# wifi-gps.net
KiCad netlist of a schematic drawn in Altium Designer
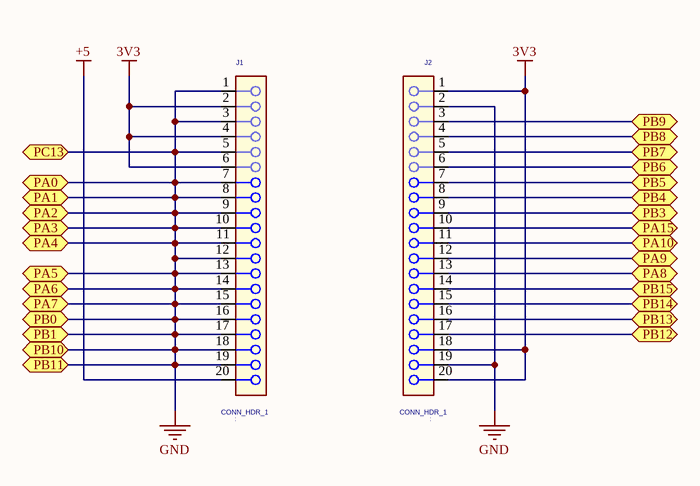
[diagram p0: wifi-gps.SchDoc]

(export (version "E")
  (design (tool "Eeschema 10.0.6"))
  (components
    (comp (ref "J1")
      (value "CONN_HDR_1")
      (footprint "SIP20-2P54-F")
      (description "CON 1X6 SKT TH 100MIL SP 344H AU 118L")
      (fields (field (name "SOURCE") "野火_STM32F103C8T6核心板_V1.0_原理图封装库_AD格式.SCHLIB"))
      (libsource (lib "yuanyu") (part "CONN_HDR_1"))
    )
    (comp (ref "J2")
      (value "CONN_HDR_1")
      (footprint "SIP20-2P54-F")
      (description "CON 1X6 SKT TH 100MIL SP 344H AU 118L")
      (fields (field (name "SOURCE") "野火_STM32F103C8T6核心板_V1.0_原理图封装库_AD格式.SCHLIB"))
      (libsource (lib "yuanyu") (part "CONN_HDR_1"))
    )
  )
  (nets
    (net (code "1") (name "+5") (class "Default")
      (node (ref "J1") (pin "20") (pinfunction "20_20") (pintype "passive"))
    )
    (net (code "2") (name "/PA8") (class "Default")
      (node (ref "J2") (pin "13") (pinfunction "13_13") (pintype "passive"))
    )
    (net (code "3") (name "/PA9") (class "Default")
      (node (ref "J2") (pin "12") (pinfunction "12_12") (pintype "passive"))
    )
    (net (code "4") (name "/PA10") (class "Default")
      (node (ref "J2") (pin "11") (pinfunction "11_11") (pintype "passive"))
    )
    (net (code "5") (name "/PA15") (class "Default")
      (node (ref "J2") (pin "10") (pinfunction "10_10") (pintype "passive"))
    )
    (net (code "6") (name "/PB3") (class "Default")
      (node (ref "J2") (pin "9") (pinfunction "9_9") (pintype "passive"))
    )
    (net (code "7") (name "/PB4") (class "Default")
      (node (ref "J2") (pin "8") (pinfunction "8_8") (pintype "passive"))
    )
    (net (code "8") (name "/PB5") (class "Default")
      (node (ref "J2") (pin "7") (pinfunction "7_7") (pintype "passive"))
    )
    (net (code "9") (name "/PB6") (class "Default")
      (node (ref "J2") (pin "6") (pinfunction "6_6") (pintype "passive"))
    )
    (net (code "10") (name "/PB7") (class "Default")
      (node (ref "J2") (pin "5") (pinfunction "5_5") (pintype "passive"))
    )
    (net (code "11") (name "/PB8") (class "Default")
      (node (ref "J2") (pin "4") (pinfunction "4_4") (pintype "passive"))
    )
    (net (code "12") (name "/PB9") (class "Default")
      (node (ref "J2") (pin "3") (pinfunction "3_3") (pintype "passive"))
    )
    (net (code "13") (name "/PB12") (class "Default")
      (node (ref "J2") (pin "17") (pinfunction "17_17") (pintype "passive"))
    )
    (net (code "14") (name "/PB13") (class "Default")
      (node (ref "J2") (pin "16") (pinfunction "16_16") (pintype "passive"))
    )
    (net (code "15") (name "/PB14") (class "Default")
      (node (ref "J2") (pin "15") (pinfunction "15_15") (pintype "passive"))
    )
    (net (code "16") (name "/PB15") (class "Default")
      (node (ref "J2") (pin "14") (pinfunction "14_14") (pintype "passive"))
    )
    (net (code "17") (name "3V3") (class "Default")
      (node (ref "J1") (pin "2") (pinfunction "2_2") (pintype "passive"))
      (node (ref "J1") (pin "4") (pinfunction "4_4") (pintype "passive"))
      (node (ref "J1") (pin "6") (pinfunction "6_6") (pintype "passive"))
      (node (ref "J2") (pin "1") (pinfunction "1_1") (pintype "passive"))
      (node (ref "J2") (pin "18") (pinfunction "18_18") (pintype "passive"))
      (node (ref "J2") (pin "20") (pinfunction "20_20") (pintype "passive"))
    )
    (net (code "18") (name "GND") (class "Default")
      (node (ref "J1") (pin "1") (pinfunction "1_1") (pintype "passive"))
      (node (ref "J1") (pin "10") (pinfunction "10_10") (pintype "passive"))
      (node (ref "J1") (pin "11") (pinfunction "11_11") (pintype "passive"))
      (node (ref "J1") (pin "12") (pinfunction "12_12") (pintype "passive"))
      (node (ref "J1") (pin "13") (pinfunction "13_13") (pintype "passive"))
      (node (ref "J1") (pin "14") (pinfunction "14_14") (pintype "passive"))
      (node (ref "J1") (pin "15") (pinfunction "15_15") (pintype "passive"))
      (node (ref "J1") (pin "16") (pinfunction "16_16") (pintype "passive"))
      (node (ref "J1") (pin "17") (pinfunction "17_17") (pintype "passive"))
      (node (ref "J1") (pin "18") (pinfunction "18_18") (pintype "passive"))
      (node (ref "J1") (pin "19") (pinfunction "19_19") (pintype "passive"))
      (node (ref "J1") (pin "3") (pinfunction "3_3") (pintype "passive"))
      (node (ref "J1") (pin "5") (pinfunction "5_5") (pintype "passive"))
      (node (ref "J1") (pin "7") (pinfunction "7_7") (pintype "passive"))
      (node (ref "J1") (pin "8") (pinfunction "8_8") (pintype "passive"))
      (node (ref "J1") (pin "9") (pinfunction "9_9") (pintype "passive"))
      (node (ref "J2") (pin "19") (pinfunction "19_19") (pintype "passive"))
      (node (ref "J2") (pin "2") (pinfunction "2_2") (pintype "passive"))
    )
  )
)
